# ArduSensor-Light.net
KiCad netlist of a schematic drawn in EAGLE
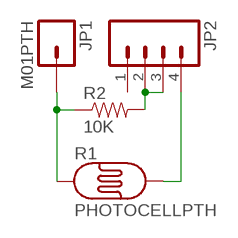
[diagram p0: schematic, sheet 1]

(export (version "E")
  (design (tool "Eeschema 10.0.6"))
  (components
    (comp (ref "JP1")
      (value "M01PTH")
      (footprint "eagle-import:1X01")
      (libsource (lib "eagle-import") (part "M01PTH"))
    )
    (comp (ref "JP2")
      (value "M04PTH")
      (footprint "eagle-import:1X04")
      (libsource (lib "eagle-import") (part "M04PTH"))
    )
    (comp (ref "R1")
      (value "PHOTOCELLPTH")
      (footprint "eagle-import:PHOTOCELL")
      (libsource (lib "eagle-import") (part "PHOTOCELLPTH"))
    )
    (comp (ref "R2")
      (value "10K")
      (footprint "eagle-import:AXIAL-0.3")
      (libsource (lib "eagle-import") (part "RESISTORAXIAL-0.3"))
    )
  )
  (nets
    (net (code "1") (name "Net-(R1-P$1)") (class "Default")
      (node (ref "JP1") (pin "1") (pinfunction "1_1") (pintype "passive"))
      (node (ref "R1") (pin "1") (pinfunction "P$1_1") (pintype "bidirectional"))
      (node (ref "R2") (pin "P$1") (pinfunction "1_P$1") (pintype "passive"))
    )
    (net (code "2") (name "Net-(R1-P$2)") (class "Default")
      (node (ref "JP2") (pin "4") (pinfunction "4_4") (pintype "passive"))
      (node (ref "R1") (pin "2") (pinfunction "P$2_2") (pintype "bidirectional"))
    )
    (net (code "3") (name "Net-(R2-2)") (class "Default")
      (node (ref "JP2") (pin "2") (pinfunction "2_2") (pintype "passive"))
      (node (ref "JP2") (pin "3") (pinfunction "3_3") (pintype "passive"))
      (node (ref "R2") (pin "P$2") (pinfunction "2_P$2") (pintype "passive"))
    )
    (net (code "4") (name "unconnected-(JP2-Pad1)") (class "Default")
      (node (ref "JP2") (pin "1") (pinfunction "1_1") (pintype "passive"))
    )
  )
)
